# altium-nano-debug.net
KiCad netlist of a schematic drawn in Altium Designer
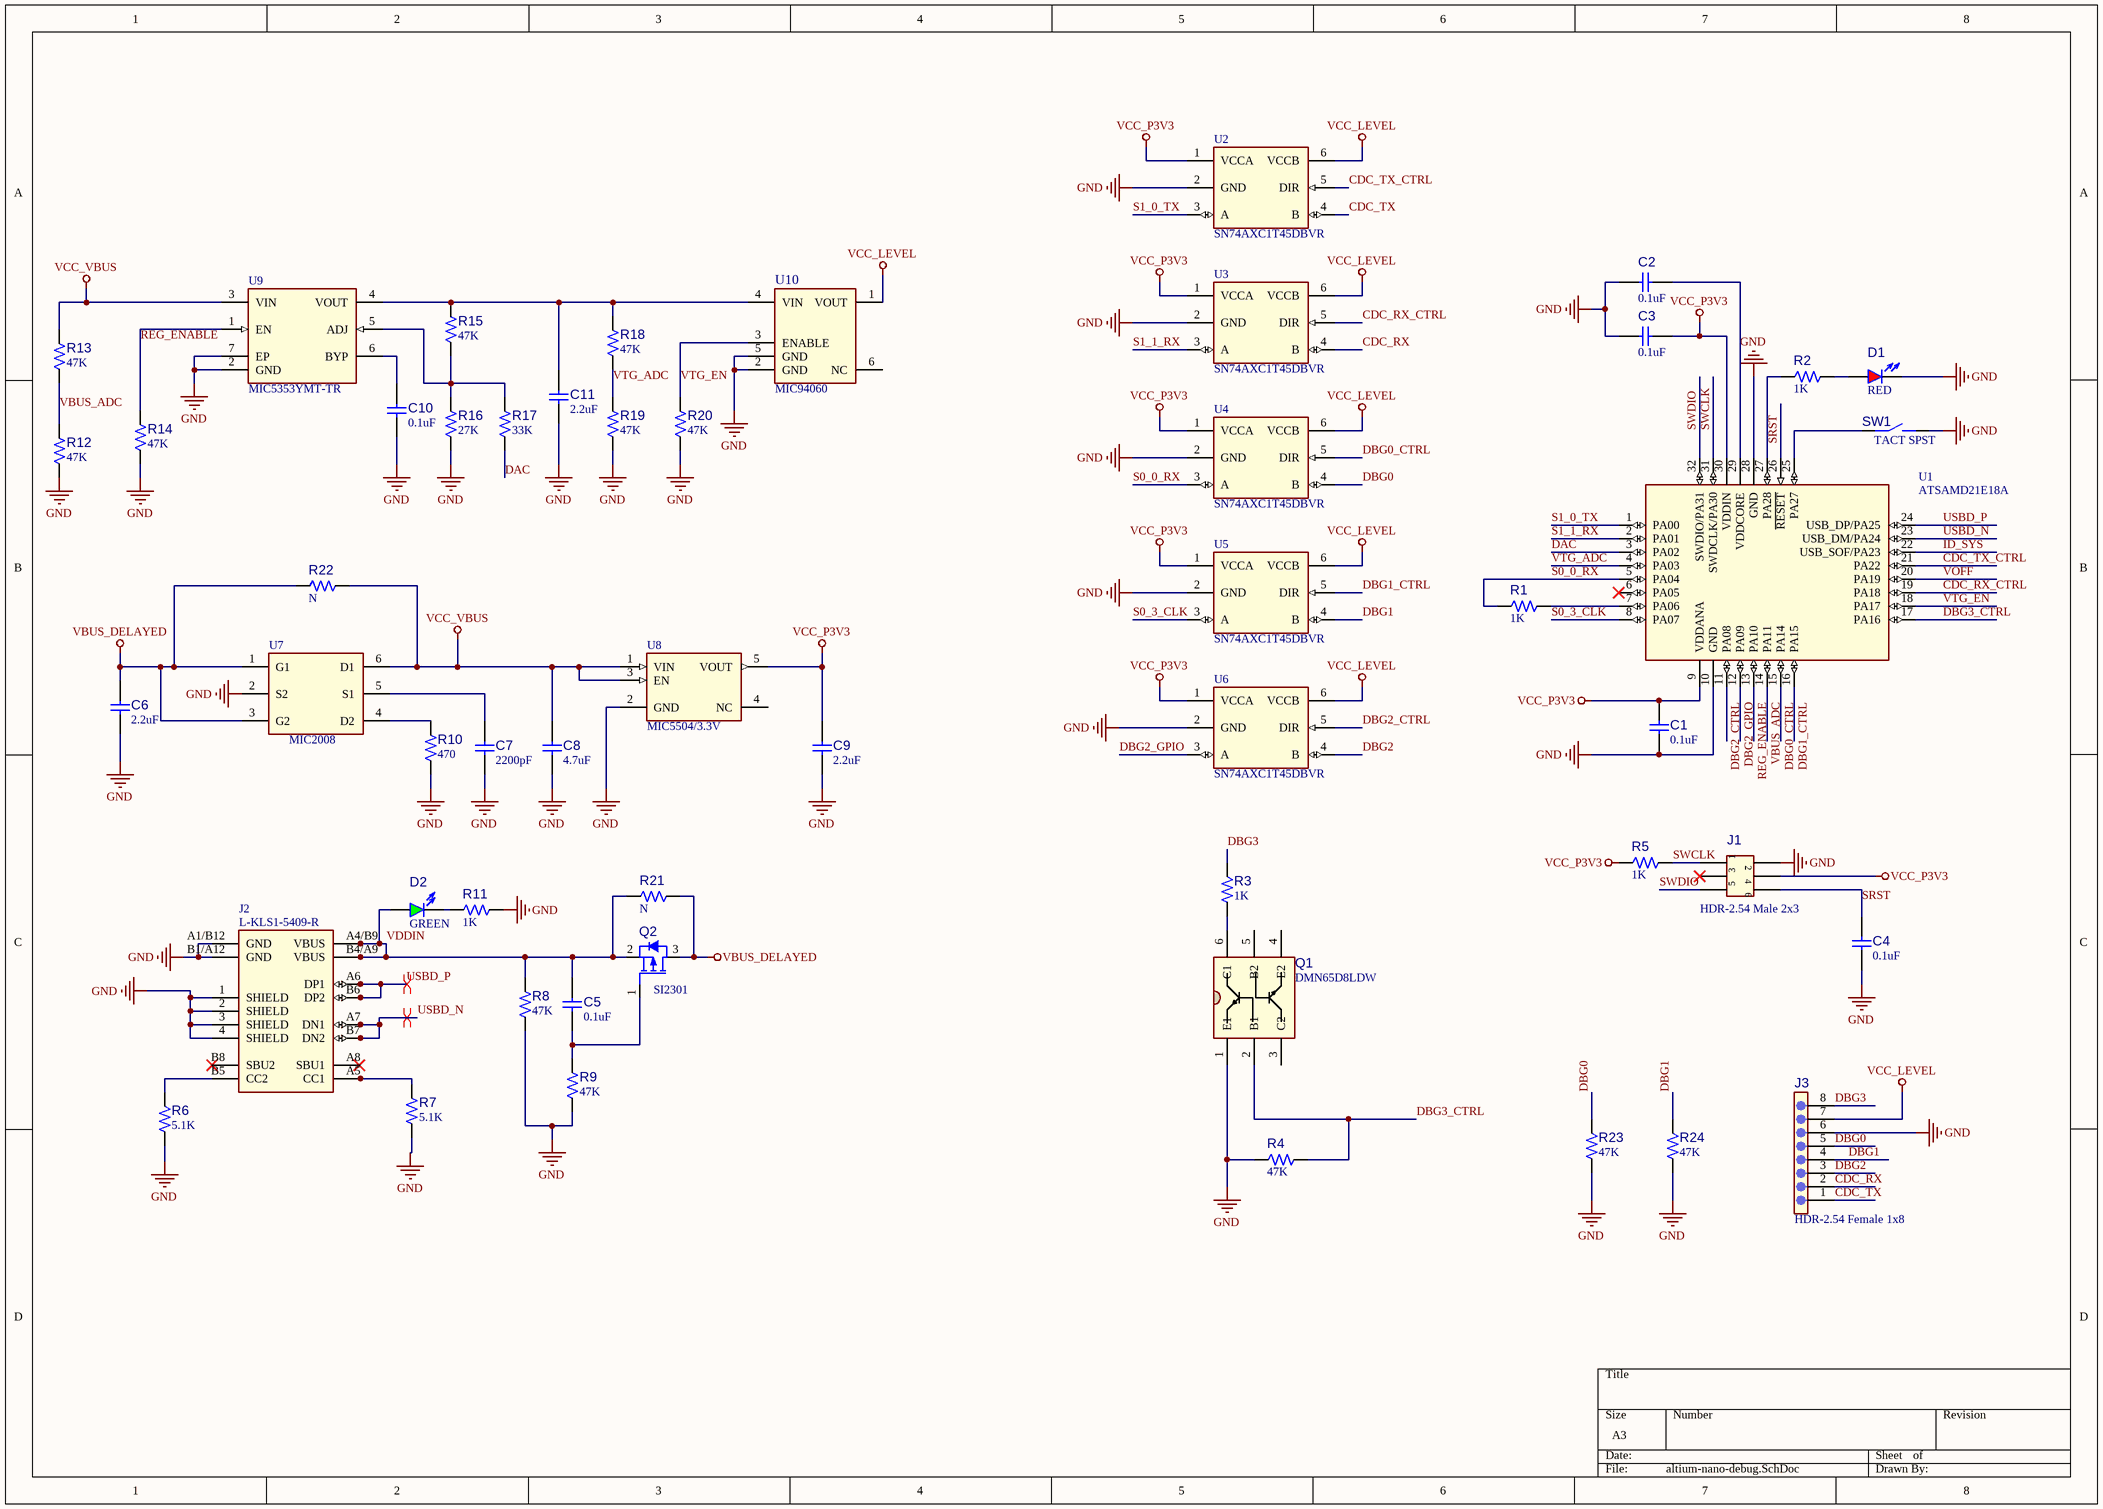
[diagram p0: altium-nano-debug.SchDoc]

(export (version "E")
  (design (tool "Eeschema 10.0.6"))
  (components
    (comp (ref "C1")
      (value "0.1uF")
      (footprint "CAP_C_0603")
      (fields (field (name "TOLERANCE") "20%") (field (name "Comment") "Capacitor NP"))
      (libsource (lib "MCHP-CDB") (part "Capacitor NP"))
    )
    (comp (ref "C2")
      (value "0.1uF")
      (footprint "CAP_C_0603")
      (fields (field (name "TOLERANCE") "20%") (field (name "Comment") "Capacitor NP"))
      (libsource (lib "MCHP-CDB") (part "Capacitor NP"))
    )
    (comp (ref "C3")
      (value "0.1uF")
      (footprint "CAP_C_0603")
      (fields (field (name "TOLERANCE") "20%") (field (name "Comment") "Capacitor NP"))
      (libsource (lib "MCHP-CDB") (part "Capacitor NP"))
    )
    (comp (ref "C4")
      (value "0.1uF")
      (footprint "CAP_C_0603")
      (fields (field (name "TOLERANCE") "20%") (field (name "Comment") "Capacitor NP"))
      (libsource (lib "MCHP-CDB") (part "Capacitor NP"))
    )
    (comp (ref "C5")
      (value "0.1uF")
      (footprint "CAP_C_0603")
      (fields (field (name "TOLERANCE") "20%") (field (name "Comment") "Capacitor NP"))
      (libsource (lib "MCHP-CDB") (part "Capacitor NP"))
    )
    (comp (ref "C6")
      (value "2.2uF")
      (footprint "CAP_C_0603")
      (fields (field (name "TOLERANCE") "20%") (field (name "Comment") "Capacitor NP"))
      (libsource (lib "MCHP-CDB") (part "Capacitor NP"))
    )
    (comp (ref "C7")
      (value "2200pF")
      (footprint "CAP_C_0603")
      (fields (field (name "TOLERANCE") "20%") (field (name "Comment") "Capacitor NP"))
      (libsource (lib "MCHP-CDB") (part "Capacitor NP"))
    )
    (comp (ref "C8")
      (value "4.7uF")
      (footprint "CAP_C_0603")
      (fields (field (name "TOLERANCE") "20%") (field (name "Comment") "Capacitor NP"))
      (libsource (lib "MCHP-CDB") (part "Capacitor NP"))
    )
    (comp (ref "C9")
      (value "2.2uF")
      (footprint "CAP_C_0603")
      (fields (field (name "TOLERANCE") "20%") (field (name "Comment") "Capacitor NP"))
      (libsource (lib "MCHP-CDB") (part "Capacitor NP"))
    )
    (comp (ref "C10")
      (value "0.1uF")
      (footprint "CAP_C_0603")
      (fields (field (name "TOLERANCE") "20%") (field (name "Comment") "Capacitor NP"))
      (libsource (lib "MCHP-CDB") (part "Capacitor NP"))
    )
    (comp (ref "C11")
      (value "2.2uF")
      (footprint "CAP_C_0603")
      (fields (field (name "TOLERANCE") "20%") (field (name "Comment") "Capacitor NP"))
      (libsource (lib "MCHP-CDB") (part "Capacitor NP"))
    )
    (comp (ref "D1")
      (value "RED")
      (footprint "LED_0603_Yellow")
      (description "LED")
      (fields (field (name "POWER") "100mW") (field (name "Comment") "LED_red"))
      (libsource (lib "MCHP-CDB") (part "LED_red"))
    )
    (comp (ref "D2")
      (value "GREEN")
      (footprint "LED_0603_GREEN")
      (description "LED")
      (fields
        (field (name "POWER") "90mW")
        (field (name "Comment") "LED_green")
        (field (name "OWNER") "Severino Balong Jr.")
      )
      (libsource (lib "MCHP-CDB") (part "LED_green"))
    )
    (comp (ref "J1")
      (value "HDR-2.54 Male 2x3")
      (footprint "HDR_M_2.54_2x3")
      (fields (field (name "Comment") "Header 2x3"))
      (libsource (lib "MCHP-CDB") (part "Header 2x3"))
    )
    (comp (ref "J2")
      (value "CON USB2.0-C RCPT SMD RA KLS KLS1-5409")
      (footprint "CON_USB2.0-C_RCPT_SMD_RA_KLS_KLS1-5409")
      (fields (field (name "VOLTAGE") "100V AC") (field (name "MANUFACTURER PART NUMBER 1") "L-KLS1-5409-R"))
      (libsource (lib "MCHP-CDB") (part "CON USB2.0-C RCPT SMD RA KLS KLS1-5409"))
    )
    (comp (ref "J3")
      (value "HDR-2.54 Female 1x8")
      (footprint "HDR_F_2.54_1x8_RA")
      (description "Header 1x8")
      (fields (field (name "OWNER") "Bogdan Popescu"))
      (libsource (lib "MCHP-CDB") (part "Header 1x8"))
    )
    (comp (ref "Q1")
      (value "DMN65D8LDW")
      (footprint "SOT-363")
      (description "ADC")
      (fields
        (field (name "POWER") "200mW")
        (field (name "Comment") "BC847BS-7-F SOT-363")
        (field (name "OWNER") "Jose Garcia")
      )
      (libsource (lib "MCHP-CDB") (part "BC847BS-7-F SOT-363"))
    )
    (comp (ref "Q2")
      (value "SI2301")
      (footprint "SOT-23-3")
      (description "Transistor MOS")
      (fields (field (name "POWER") "1.3W") (field (name "Comment") "Transistor MOS-P GSD"))
      (libsource (lib "MCHP-CDB") (part "Transistor MOS-P GSD"))
    )
    (comp (ref "R1")
      (value "1K")
      (footprint "RES_C_0603")
      (description "Resistor")
      (fields (field (name "VOLTAGE") "50V") (field (name "POWER") "1/10W"))
      (libsource (lib "MCHP-CDB") (part "Resistor"))
    )
    (comp (ref "R2")
      (value "1K")
      (footprint "RES_C_0603")
      (description "Resistor")
      (fields (field (name "VOLTAGE") "50V") (field (name "POWER") "1/10W"))
      (libsource (lib "MCHP-CDB") (part "Resistor"))
    )
    (comp (ref "R3")
      (value "1K")
      (footprint "RES_C_0603")
      (description "Resistor")
      (fields (field (name "VOLTAGE") "50V") (field (name "POWER") "1/10W"))
      (libsource (lib "MCHP-CDB") (part "Resistor"))
    )
    (comp (ref "R4")
      (value "47K")
      (footprint "RES_C_0603")
      (description "Resistor")
      (fields (field (name "VOLTAGE") "50V") (field (name "POWER") "1/10W"))
      (libsource (lib "MCHP-CDB") (part "Resistor"))
    )
    (comp (ref "R5")
      (value "1K")
      (footprint "RES_C_0603")
      (description "Resistor")
      (fields (field (name "VOLTAGE") "50V") (field (name "POWER") "1/10W"))
      (libsource (lib "MCHP-CDB") (part "Resistor"))
    )
    (comp (ref "R6")
      (value "5.1K")
      (footprint "RES_C_0603")
      (description "Resistor")
      (fields (field (name "VOLTAGE") "50V") (field (name "POWER") "1/10W"))
      (libsource (lib "MCHP-CDB") (part "Resistor"))
    )
    (comp (ref "R7")
      (value "5.1K")
      (footprint "RES_C_0603")
      (description "Resistor")
      (fields (field (name "VOLTAGE") "50V") (field (name "POWER") "1/10W"))
      (libsource (lib "MCHP-CDB") (part "Resistor"))
    )
    (comp (ref "R8")
      (value "47K")
      (footprint "RES_C_0603")
      (description "Resistor")
      (fields (field (name "VOLTAGE") "50V") (field (name "POWER") "1/10W"))
      (libsource (lib "MCHP-CDB") (part "Resistor"))
    )
    (comp (ref "R9")
      (value "47K")
      (footprint "RES_C_0603")
      (description "Resistor")
      (fields (field (name "VOLTAGE") "50V") (field (name "POWER") "1/10W"))
      (libsource (lib "MCHP-CDB") (part "Resistor"))
    )
    (comp (ref "R10")
      (value "470")
      (footprint "RES_C_0603")
      (description "Resistor")
      (fields (field (name "VOLTAGE") "50V") (field (name "POWER") "1/10W"))
      (libsource (lib "MCHP-CDB") (part "Resistor"))
    )
    (comp (ref "R11")
      (value "1K")
      (footprint "RES_C_0603")
      (description "Resistor")
      (fields (field (name "VOLTAGE") "50V") (field (name "POWER") "1/10W"))
      (libsource (lib "MCHP-CDB") (part "Resistor"))
    )
    (comp (ref "R12")
      (value "47K")
      (footprint "RES_C_0603")
      (description "Resistor")
      (fields (field (name "VOLTAGE") "50V") (field (name "POWER") "1/10W"))
      (libsource (lib "MCHP-CDB") (part "Resistor"))
    )
    (comp (ref "R13")
      (value "47K")
      (footprint "RES_C_0603")
      (description "Resistor")
      (fields (field (name "VOLTAGE") "50V") (field (name "POWER") "1/10W"))
      (libsource (lib "MCHP-CDB") (part "Resistor"))
    )
    (comp (ref "R14")
      (value "47K")
      (footprint "RES_C_0603")
      (description "Resistor")
      (fields (field (name "VOLTAGE") "50V") (field (name "POWER") "1/10W"))
      (libsource (lib "MCHP-CDB") (part "Resistor"))
    )
    (comp (ref "R15")
      (value "47K")
      (footprint "RES_C_0603")
      (description "Resistor")
      (fields (field (name "VOLTAGE") "50V") (field (name "POWER") "1/10W"))
      (libsource (lib "MCHP-CDB") (part "Resistor"))
    )
    (comp (ref "R16")
      (value "27K")
      (footprint "RES_C_0603")
      (description "Resistor")
      (fields (field (name "VOLTAGE") "50V") (field (name "POWER") "1/10W"))
      (libsource (lib "MCHP-CDB") (part "Resistor"))
    )
    (comp (ref "R17")
      (value "33K")
      (footprint "RES_C_0603")
      (description "Resistor")
      (fields (field (name "VOLTAGE") "50V") (field (name "POWER") "1/10W"))
      (libsource (lib "MCHP-CDB") (part "Resistor"))
    )
    (comp (ref "R18")
      (value "47K")
      (footprint "RES_C_0603")
      (description "Resistor")
      (fields (field (name "VOLTAGE") "50V") (field (name "POWER") "1/10W"))
      (libsource (lib "MCHP-CDB") (part "Resistor"))
    )
    (comp (ref "R19")
      (value "47K")
      (footprint "RES_C_0603")
      (description "Resistor")
      (fields (field (name "VOLTAGE") "50V") (field (name "POWER") "1/10W"))
      (libsource (lib "MCHP-CDB") (part "Resistor"))
    )
    (comp (ref "R20")
      (value "47K")
      (footprint "RES_C_0603")
      (description "Resistor")
      (fields (field (name "VOLTAGE") "50V") (field (name "POWER") "1/10W"))
      (libsource (lib "MCHP-CDB") (part "Resistor"))
    )
    (comp (ref "R21")
      (value "N")
      (footprint "RES_C_0603")
      (description "Resistor")
      (fields (field (name "VOLTAGE") "50V") (field (name "POWER") "1/10W"))
      (libsource (lib "MCHP-CDB") (part "Resistor"))
    )
    (comp (ref "R22")
      (value "N")
      (footprint "RES_C_0603")
      (description "Resistor")
      (fields (field (name "VOLTAGE") "50V") (field (name "POWER") "1/10W"))
      (libsource (lib "MCHP-CDB") (part "Resistor"))
    )
    (comp (ref "R23")
      (value "47K")
      (footprint "RES_C_0603")
      (description "Resistor")
      (fields (field (name "VOLTAGE") "50V") (field (name "POWER") "1/10W"))
      (libsource (lib "MCHP-CDB") (part "Resistor"))
    )
    (comp (ref "R24")
      (value "47K")
      (footprint "RES_C_0603")
      (description "Resistor")
      (fields (field (name "VOLTAGE") "50V") (field (name "POWER") "1/10W"))
      (libsource (lib "MCHP-CDB") (part "Resistor"))
    )
    (comp (ref "SW1")
      (value "TACT SPST")
      (footprint "SW_TACT_SMD_CK_KSR231GLFS")
      (description "Switch")
      (fields
        (field (name "VOLTAGE") "24V")
        (field (name "Comment") "Switch 2 Pin")
        (field (name "OWNER") "Jamus Griego")
      )
      (libsource (lib "MCHP-CDB") (part "Switch 2 Pin"))
    )
    (comp (ref "U1")
      (value "ATSAMD21E18A")
      (footprint "TQFP-32_7x7")
      (description "Microcontroller")
      (fields (field (name "Comment") "ATSAMD21E TQFP-32") (field (name "OWNER") "Vegard  Leksas"))
      (libsource (lib "MCHP-CDB") (part "ATSAMD21E TQFP-32"))
    )
    (comp (ref "U2")
      (value "SN74AXC1T45DBVR")
      (footprint "SOT-23-6")
      (fields (field (name "Comment") "SN74LVC1T45MDCKREP SC-70-6") (field (name "OWNER") "Dragos Danaila"))
      (libsource (lib "MCHP-CDB") (part "SN74LVC1T45MDCKREP SC-70-6"))
    )
    (comp (ref "U3")
      (value "SN74AXC1T45DBVR")
      (footprint "SOT-23-6")
      (fields (field (name "Comment") "SN74LVC1T45MDCKREP SC-70-6") (field (name "OWNER") "Dragos Danaila"))
      (libsource (lib "MCHP-CDB") (part "SN74LVC1T45MDCKREP SC-70-6"))
    )
    (comp (ref "U4")
      (value "SN74AXC1T45DBVR")
      (footprint "SOT-23-6")
      (fields (field (name "Comment") "SN74LVC1T45MDCKREP SC-70-6") (field (name "OWNER") "Dragos Danaila"))
      (libsource (lib "MCHP-CDB") (part "SN74LVC1T45MDCKREP SC-70-6"))
    )
    (comp (ref "U5")
      (value "SN74AXC1T45DBVR")
      (footprint "SOT-23-6")
      (fields (field (name "Comment") "SN74LVC1T45MDCKREP SC-70-6") (field (name "OWNER") "Dragos Danaila"))
      (libsource (lib "MCHP-CDB") (part "SN74LVC1T45MDCKREP SC-70-6"))
    )
    (comp (ref "U6")
      (value "SN74AXC1T45DBVR")
      (footprint "SOT-23-6")
      (fields (field (name "Comment") "SN74LVC1T45MDCKREP SC-70-6") (field (name "OWNER") "Dragos Danaila"))
      (libsource (lib "MCHP-CDB") (part "SN74LVC1T45MDCKREP SC-70-6"))
    )
    (comp (ref "U7")
      (value "MIC2008")
      (footprint "SOT-23-6")
      (fields (field (name "Comment") "AM3906N SOT23-6") (field (name "OWNER") "Jose Garcia"))
      (libsource (lib "MCHP-CDB") (part "AM3906N SOT23-6"))
    )
    (comp (ref "U8")
      (value "MIC5504/3.3V")
      (footprint "SOT-23-5")
      (fields (field (name "Comment") "MIC55XX-X.X SOT23-5") (field (name "OWNER") "Cristina Salanti"))
      (libsource (lib "MCHP-CDB") (part "MIC55XX-X.X SOT23-5"))
    )
    (comp (ref "U9")
      (value "MIC5353YMT-TR")
      (footprint "MLF-6 1.6X1.6mm")
      (description "LDO Regulator")
      (fields (field (name "Comment") "MIC53XX ADJ MLF-6") (field (name "OWNER") "Mark Loper"))
      (libsource (lib "MCHP-CDB") (part "MIC53XX ADJ MLF-6"))
    )
    (comp (ref "U10")
      (value "MIC94060")
      (footprint "SC-70-6")
      (fields (field (name "Comment") "MIC94060Y-SC70-6") (field (name "OWNER") "Sam Charles"))
      (libsource (lib "MCHP-CDB") (part "MIC94060Y-SC70-6"))
    )
  )
  (nets
    (net (code "1") (name "/CDC_RX") (class "Default")
      (node (ref "J3") (pin "2") (pinfunction "2_2") (pintype "passive"))
      (node (ref "U3") (pin "4") (pinfunction "B_4") (pintype "bidirectional"))
    )
    (net (code "2") (name "/CDC_RX_CTRL") (class "Default")
      (node (ref "U1") (pin "19") (pinfunction "PA18_19") (pintype "bidirectional"))
      (node (ref "U3") (pin "5") (pinfunction "DIR_5") (pintype "input"))
    )
    (net (code "3") (name "/CDC_TX") (class "Default")
      (node (ref "J3") (pin "1") (pinfunction "1_1") (pintype "passive"))
      (node (ref "U2") (pin "4") (pinfunction "B_4") (pintype "bidirectional"))
    )
    (net (code "4") (name "/CDC_TX_CTRL") (class "Default")
      (node (ref "U1") (pin "21") (pinfunction "PA22_21") (pintype "bidirectional"))
      (node (ref "U2") (pin "5") (pinfunction "DIR_5") (pintype "input"))
    )
    (net (code "5") (name "/DAC") (class "Default")
      (node (ref "R17") (pin "2") (pinfunction "2_2") (pintype "passive"))
      (node (ref "U1") (pin "3") (pinfunction "PA02_3") (pintype "bidirectional"))
    )
    (net (code "6") (name "/DBG0") (class "Default")
      (node (ref "J3") (pin "5") (pinfunction "5_5") (pintype "passive"))
      (node (ref "R23") (pin "2") (pinfunction "2_2") (pintype "passive"))
      (node (ref "U4") (pin "4") (pinfunction "B_4") (pintype "bidirectional"))
    )
    (net (code "7") (name "/DBG0_CTRL") (class "Default")
      (node (ref "U1") (pin "15") (pinfunction "PA14_15") (pintype "bidirectional"))
      (node (ref "U4") (pin "5") (pinfunction "DIR_5") (pintype "input"))
    )
    (net (code "8") (name "/DBG1") (class "Default")
      (node (ref "J3") (pin "4") (pinfunction "4_4") (pintype "passive"))
      (node (ref "R24") (pin "2") (pinfunction "2_2") (pintype "passive"))
      (node (ref "U5") (pin "4") (pinfunction "B_4") (pintype "bidirectional"))
    )
    (net (code "9") (name "/DBG1_CTRL") (class "Default")
      (node (ref "U1") (pin "16") (pinfunction "PA15_16") (pintype "bidirectional"))
      (node (ref "U5") (pin "5") (pinfunction "DIR_5") (pintype "input"))
    )
    (net (code "10") (name "/DBG2") (class "Default")
      (node (ref "J3") (pin "3") (pinfunction "3_3") (pintype "passive"))
      (node (ref "U6") (pin "4") (pinfunction "B_4") (pintype "bidirectional"))
    )
    (net (code "11") (name "/DBG2_CTRL") (class "Default")
      (node (ref "U1") (pin "11") (pinfunction "PA08_11") (pintype "bidirectional"))
      (node (ref "U6") (pin "5") (pinfunction "DIR_5") (pintype "input"))
    )
    (net (code "12") (name "/DBG2_GPIO") (class "Default")
      (node (ref "U1") (pin "12") (pinfunction "PA09_12") (pintype "bidirectional"))
      (node (ref "U6") (pin "3") (pinfunction "A_3") (pintype "bidirectional"))
    )
    (net (code "13") (name "/DBG3") (class "Default")
      (node (ref "J3") (pin "8") (pinfunction "8_8") (pintype "passive"))
      (node (ref "R3") (pin "2") (pinfunction "2_2") (pintype "passive"))
    )
    (net (code "14") (name "/DBG3_CTRL") (class "Default")
      (node (ref "Q1") (pin "2") (pinfunction "B1_2") (pintype "passive"))
      (node (ref "R4") (pin "2") (pinfunction "2_2") (pintype "passive"))
      (node (ref "U1") (pin "17") (pinfunction "PA16_17") (pintype "bidirectional"))
    )
    (net (code "15") (name "/ID_SYS") (class "Default")
      (node (ref "U1") (pin "22") (pinfunction "USB_SOF/PA23_22") (pintype "bidirectional"))
    )
    (net (code "16") (name "/REG_ENABLE") (class "Default")
      (node (ref "R14") (pin "2") (pinfunction "2_2") (pintype "passive"))
      (node (ref "U1") (pin "13") (pinfunction "PA10_13") (pintype "bidirectional"))
      (node (ref "U9") (pin "1") (pinfunction "EN_1") (pintype "input"))
    )
    (net (code "17") (name "/S0_0_RX") (class "Default")
      (node (ref "R1") (pin "1") (pinfunction "1_1") (pintype "passive"))
      (node (ref "U1") (pin "5") (pinfunction "PA04_5") (pintype "bidirectional"))
      (node (ref "U4") (pin "3") (pinfunction "A_3") (pintype "bidirectional"))
    )
    (net (code "18") (name "/S0_3_CLK") (class "Default")
      (node (ref "U1") (pin "8") (pinfunction "PA07_8") (pintype "bidirectional"))
      (node (ref "U5") (pin "3") (pinfunction "A_3") (pintype "bidirectional"))
    )
    (net (code "19") (name "/S1_0_TX") (class "Default")
      (node (ref "U1") (pin "1") (pinfunction "PA00_1") (pintype "bidirectional"))
      (node (ref "U2") (pin "3") (pinfunction "A_3") (pintype "bidirectional"))
    )
    (net (code "20") (name "/S1_1_RX") (class "Default")
      (node (ref "U1") (pin "2") (pinfunction "PA01_2") (pintype "bidirectional"))
      (node (ref "U3") (pin "3") (pinfunction "A_3") (pintype "bidirectional"))
    )
    (net (code "21") (name "/SRST") (class "Default")
      (node (ref "C4") (pin "2") (pinfunction "2_2") (pintype "passive"))
      (node (ref "J1") (pin "6") (pinfunction "6_6") (pintype "passive"))
      (node (ref "U1") (pin "26") (pinfunction "~{RESET}_26") (pintype "input"))
    )
    (net (code "22") (name "/SWCLK") (class "Default")
      (node (ref "J1") (pin "1") (pinfunction "1_1") (pintype "passive"))
      (node (ref "R5") (pin "1") (pinfunction "1_1") (pintype "passive"))
      (node (ref "U1") (pin "31") (pinfunction "SWDCLK/PA30_31") (pintype "bidirectional"))
    )
    (net (code "23") (name "/SWDIO") (class "Default")
      (node (ref "J1") (pin "5") (pinfunction "5_5") (pintype "passive"))
      (node (ref "U1") (pin "32") (pinfunction "SWDIO/PA31_32") (pintype "bidirectional"))
    )
    (net (code "24") (name "/USBD_N") (class "Default")
      (node (ref "J2") (pin "A7") (pinfunction "DN1_A7") (pintype "bidirectional"))
      (node (ref "J2") (pin "B7") (pinfunction "DN2_B7") (pintype "bidirectional"))
      (node (ref "U1") (pin "23") (pinfunction "USB_DM/PA24_23") (pintype "bidirectional"))
    )
    (net (code "25") (name "/USBD_P") (class "Default")
      (node (ref "J2") (pin "A6") (pinfunction "DP1_A6") (pintype "bidirectional"))
      (node (ref "J2") (pin "B6") (pinfunction "DP2_B6") (pintype "bidirectional"))
      (node (ref "U1") (pin "24") (pinfunction "USB_DP/PA25_24") (pintype "bidirectional"))
    )
    (net (code "26") (name "/VBUS_ADC") (class "Default")
      (node (ref "R12") (pin "2") (pinfunction "2_2") (pintype "passive"))
      (node (ref "R13") (pin "1") (pinfunction "1_1") (pintype "passive"))
      (node (ref "U1") (pin "14") (pinfunction "PA11_14") (pintype "bidirectional"))
    )
    (net (code "27") (name "/VDDIN") (class "Default")
      (node (ref "C5") (pin "1") (pinfunction "1_1") (pintype "passive"))
      (node (ref "D2") (pin "1") (pinfunction "A_1") (pintype "passive"))
      (node (ref "J2") (pin "A4/B9") (pinfunction "VBUS_A4/B9") (pintype "power_in"))
      (node (ref "J2") (pin "B4/A9") (pinfunction "VBUS_B4/A9") (pintype "power_in"))
      (node (ref "Q2") (pin "2") (pinfunction "S_2") (pintype "passive"))
      (node (ref "R21") (pin "2") (pinfunction "2_2") (pintype "passive"))
      (node (ref "R8") (pin "2") (pinfunction "2_2") (pintype "passive"))
    )
    (net (code "28") (name "/VOFF") (class "Default")
      (node (ref "U1") (pin "20") (pinfunction "PA19_20") (pintype "bidirectional"))
    )
    (net (code "29") (name "/VTG_ADC") (class "Default")
      (node (ref "R18") (pin "1") (pinfunction "1_1") (pintype "passive"))
      (node (ref "R19") (pin "2") (pinfunction "2_2") (pintype "passive"))
      (node (ref "U1") (pin "4") (pinfunction "PA03_4") (pintype "bidirectional"))
    )
    (net (code "30") (name "/VTG_EN") (class "Default")
      (node (ref "R20") (pin "2") (pinfunction "2_2") (pintype "passive"))
      (node (ref "U1") (pin "18") (pinfunction "PA17_18") (pintype "bidirectional"))
      (node (ref "U10") (pin "3") (pinfunction "ENABLE_3") (pintype "passive"))
    )
    (net (code "31") (name "GND") (class "Default")
      (node (ref "C1") (pin "1") (pinfunction "1_1") (pintype "passive"))
      (node (ref "C10") (pin "2") (pinfunction "2_2") (pintype "passive"))
      (node (ref "C11") (pin "2") (pinfunction "2_2") (pintype "passive"))
      (node (ref "C2") (pin "1") (pinfunction "1_1") (pintype "passive"))
      (node (ref "C3") (pin "1") (pinfunction "1_1") (pintype "passive"))
      (node (ref "C4") (pin "1") (pinfunction "1_1") (pintype "passive"))
      (node (ref "C6") (pin "2") (pinfunction "2_2") (pintype "passive"))
      (node (ref "C7") (pin "2") (pinfunction "2_2") (pintype "passive"))
      (node (ref "C8") (pin "2") (pinfunction "2_2") (pintype "passive"))
      (node (ref "C9") (pin "2") (pinfunction "2_2") (pintype "passive"))
      (node (ref "D1") (pin "2") (pinfunction "K_2") (pintype "passive"))
      (node (ref "J1") (pin "2") (pinfunction "2_2") (pintype "passive"))
      (node (ref "J2") (pin "1") (pinfunction "SHIELD_1") (pintype "passive"))
      (node (ref "J2") (pin "2") (pinfunction "SHIELD_2") (pintype "passive"))
      (node (ref "J2") (pin "3") (pinfunction "SHIELD_3") (pintype "passive"))
      (node (ref "J2") (pin "4") (pinfunction "SHIELD_4") (pintype "passive"))
      (node (ref "J2") (pin "A1/B12") (pinfunction "GND_A1/B12") (pintype "power_in"))
      (node (ref "J2") (pin "B1/A12") (pinfunction "GND_B1/A12") (pintype "power_in"))
      (node (ref "J3") (pin "6") (pinfunction "6_6") (pintype "passive"))
      (node (ref "Q1") (pin "1") (pinfunction "E1_1") (pintype "passive"))
      (node (ref "R10") (pin "1") (pinfunction "1_1") (pintype "passive"))
      (node (ref "R11") (pin "1") (pinfunction "1_1") (pintype "passive"))
      (node (ref "R12") (pin "1") (pinfunction "1_1") (pintype "passive"))
      (node (ref "R14") (pin "1") (pinfunction "1_1") (pintype "passive"))
      (node (ref "R16") (pin "1") (pinfunction "1_1") (pintype "passive"))
      (node (ref "R19") (pin "1") (pinfunction "1_1") (pintype "passive"))
      (node (ref "R20") (pin "1") (pinfunction "1_1") (pintype "passive"))
      (node (ref "R23") (pin "1") (pinfunction "1_1") (pintype "passive"))
      (node (ref "R24") (pin "1") (pinfunction "1_1") (pintype "passive"))
      (node (ref "R4") (pin "1") (pinfunction "1_1") (pintype "passive"))
      (node (ref "R6") (pin "2") (pinfunction "2_2") (pintype "passive"))
      (node (ref "R7") (pin "2") (pinfunction "2_2") (pintype "passive"))
      (node (ref "R8") (pin "1") (pinfunction "1_1") (pintype "passive"))
      (node (ref "R9") (pin "1") (pinfunction "1_1") (pintype "passive"))
      (node (ref "SW1") (pin "2") (pinfunction "2_2") (pintype "passive"))
      (node (ref "U1") (pin "10") (pinfunction "GND_10") (pintype "power_in"))
      (node (ref "U1") (pin "28") (pinfunction "GND_28") (pintype "power_in"))
      (node (ref "U10") (pin "2") (pinfunction "GND_2") (pintype "passive"))
      (node (ref "U10") (pin "5") (pinfunction "GND_5") (pintype "passive"))
      (node (ref "U2") (pin "2") (pinfunction "GND_2") (pintype "power_in"))
      (node (ref "U3") (pin "2") (pinfunction "GND_2") (pintype "power_in"))
      (node (ref "U4") (pin "2") (pinfunction "GND_2") (pintype "power_in"))
      (node (ref "U5") (pin "2") (pinfunction "GND_2") (pintype "power_in"))
      (node (ref "U6") (pin "2") (pinfunction "GND_2") (pintype "power_in"))
      (node (ref "U7") (pin "2") (pinfunction "S2_2") (pintype "power_in"))
      (node (ref "U8") (pin "2") (pinfunction "GND_2") (pintype "passive"))
      (node (ref "U9") (pin "2") (pinfunction "GND_2") (pintype "power_in"))
      (node (ref "U9") (pin "7") (pinfunction "EP_7") (pintype "passive"))
    )
    (net (code "32") (name "Net-(D1-A)") (class "Default")
      (node (ref "D1") (pin "1") (pinfunction "A_1") (pintype "passive"))
      (node (ref "R2") (pin "1") (pinfunction "1_1") (pintype "passive"))
    )
    (net (code "33") (name "Net-(D2-K)") (class "Default")
      (node (ref "D2") (pin "2") (pinfunction "K_2") (pintype "passive"))
      (node (ref "R11") (pin "2") (pinfunction "2_2") (pintype "passive"))
    )
    (net (code "34") (name "Net-(J2-CC1)") (class "Default")
      (node (ref "J2") (pin "A5") (pinfunction "CC1_A5") (pintype "passive"))
      (node (ref "R7") (pin "1") (pinfunction "1_1") (pintype "passive"))
    )
    (net (code "35") (name "Net-(J2-CC2)") (class "Default")
      (node (ref "J2") (pin "B5") (pinfunction "CC2_B5") (pintype "passive"))
      (node (ref "R6") (pin "1") (pinfunction "1_1") (pintype "passive"))
    )
    (net (code "36") (name "Net-(Q1-C1)") (class "Default")
      (node (ref "Q1") (pin "6") (pinfunction "C1_6") (pintype "passive"))
      (node (ref "R3") (pin "1") (pinfunction "1_1") (pintype "passive"))
    )
    (net (code "37") (name "Net-(Q2-G)") (class "Default")
      (node (ref "C5") (pin "2") (pinfunction "2_2") (pintype "passive"))
      (node (ref "Q2") (pin "1") (pinfunction "G_1") (pintype "passive"))
      (node (ref "R9") (pin "2") (pinfunction "2_2") (pintype "passive"))
    )
    (net (code "38") (name "Net-(U1-PA06)") (class "Default")
      (node (ref "R1") (pin "2") (pinfunction "2_2") (pintype "passive"))
      (node (ref "U1") (pin "7") (pinfunction "PA06_7") (pintype "bidirectional"))
    )
    (net (code "39") (name "Net-(U1-PA27)") (class "Default")
      (node (ref "SW1") (pin "1") (pinfunction "1_1") (pintype "passive"))
      (node (ref "U1") (pin "25") (pinfunction "PA27_25") (pintype "bidirectional"))
    )
    (net (code "40") (name "Net-(U1-PA28)") (class "Default")
      (node (ref "R2") (pin "2") (pinfunction "2_2") (pintype "passive"))
      (node (ref "U1") (pin "27") (pinfunction "PA28_27") (pintype "bidirectional"))
    )
    (net (code "41") (name "Net-(U1-VDDCORE)") (class "Default")
      (node (ref "C2") (pin "2") (pinfunction "2_2") (pintype "passive"))
      (node (ref "U1") (pin "29") (pinfunction "VDDCORE_29") (pintype "power_in"))
    )
    (net (code "42") (name "Net-(U7-D2)") (class "Default")
      (node (ref "R10") (pin "2") (pinfunction "2_2") (pintype "passive"))
      (node (ref "U7") (pin "4") (pinfunction "D2_4") (pintype "passive"))
    )
    (net (code "43") (name "Net-(U7-S1)") (class "Default")
      (node (ref "C7") (pin "1") (pinfunction "1_1") (pintype "passive"))
      (node (ref "U7") (pin "5") (pinfunction "S1_5") (pintype "passive"))
    )
    (net (code "44") (name "Net-(U9-ADJ)") (class "Default")
      (node (ref "R15") (pin "1") (pinfunction "1_1") (pintype "passive"))
      (node (ref "R16") (pin "2") (pinfunction "2_2") (pintype "passive"))
      (node (ref "R17") (pin "1") (pinfunction "1_1") (pintype "passive"))
      (node (ref "U9") (pin "5") (pinfunction "ADJ_5") (pintype "input"))
    )
    (net (code "45") (name "Net-(U9-BYP)") (class "Default")
      (node (ref "C10") (pin "1") (pinfunction "1_1") (pintype "passive"))
      (node (ref "U9") (pin "6") (pinfunction "BYP_6") (pintype "power_in"))
    )
    (net (code "46") (name "Net-(U10-VIN)") (class "Default")
      (node (ref "C11") (pin "1") (pinfunction "1_1") (pintype "passive"))
      (node (ref "R15") (pin "2") (pinfunction "2_2") (pintype "passive"))
      (node (ref "R18") (pin "2") (pinfunction "2_2") (pintype "passive"))
      (node (ref "U10") (pin "4") (pinfunction "VIN_4") (pintype "passive"))
      (node (ref "U9") (pin "4") (pinfunction "VOUT_4") (pintype "power_in"))
    )
    (net (code "47") (name "VBUS_DELAYED") (class "Default")
      (node (ref "C6") (pin "1") (pinfunction "1_1") (pintype "passive"))
      (node (ref "Q2") (pin "3") (pinfunction "D_3") (pintype "passive"))
      (node (ref "R21") (pin "1") (pinfunction "1_1") (pintype "passive"))
      (node (ref "R22") (pin "2") (pinfunction "2_2") (pintype "passive"))
      (node (ref "U7") (pin "1") (pinfunction "G1_1") (pintype "power_in"))
      (node (ref "U7") (pin "3") (pinfunction "G2_3") (pintype "passive"))
    )
    (net (code "48") (name "VCC_LEVEL") (class "Default")
      (node (ref "J3") (pin "7") (pinfunction "7_7") (pintype "passive"))
      (node (ref "U10") (pin "1") (pinfunction "VOUT_1") (pintype "passive"))
      (node (ref "U2") (pin "6") (pinfunction "VCCB_6") (pintype "power_in"))
      (node (ref "U3") (pin "6") (pinfunction "VCCB_6") (pintype "power_in"))
      (node (ref "U4") (pin "6") (pinfunction "VCCB_6") (pintype "power_in"))
      (node (ref "U5") (pin "6") (pinfunction "VCCB_6") (pintype "power_in"))
      (node (ref "U6") (pin "6") (pinfunction "VCCB_6") (pintype "power_in"))
    )
    (net (code "49") (name "VCC_P3V3") (class "Default")
      (node (ref "C1") (pin "2") (pinfunction "2_2") (pintype "passive"))
      (node (ref "C3") (pin "2") (pinfunction "2_2") (pintype "passive"))
      (node (ref "C9") (pin "1") (pinfunction "1_1") (pintype "passive"))
      (node (ref "J1") (pin "4") (pinfunction "4_4") (pintype "passive"))
      (node (ref "R5") (pin "2") (pinfunction "2_2") (pintype "passive"))
      (node (ref "U1") (pin "30") (pinfunction "VDDIN_30") (pintype "power_in"))
      (node (ref "U1") (pin "9") (pinfunction "VDDANA_9") (pintype "power_in"))
      (node (ref "U2") (pin "1") (pinfunction "VCCA_1") (pintype "power_in"))
      (node (ref "U3") (pin "1") (pinfunction "VCCA_1") (pintype "power_in"))
      (node (ref "U4") (pin "1") (pinfunction "VCCA_1") (pintype "power_in"))
      (node (ref "U5") (pin "1") (pinfunction "VCCA_1") (pintype "power_in"))
      (node (ref "U6") (pin "1") (pinfunction "VCCA_1") (pintype "power_in"))
      (node (ref "U8") (pin "5") (pinfunction "VOUT_5") (pintype "output"))
    )
    (net (code "50") (name "VCC_VBUS") (class "Default")
      (node (ref "C8") (pin "1") (pinfunction "1_1") (pintype "passive"))
      (node (ref "R13") (pin "2") (pinfunction "2_2") (pintype "passive"))
      (node (ref "R22") (pin "1") (pinfunction "1_1") (pintype "passive"))
      (node (ref "U7") (pin "6") (pinfunction "D1_6") (pintype "power_in"))
      (node (ref "U8") (pin "1") (pinfunction "VIN_1") (pintype "input"))
      (node (ref "U8") (pin "3") (pinfunction "EN_3") (pintype "input"))
      (node (ref "U9") (pin "3") (pinfunction "VIN_3") (pintype "power_in"))
    )
    (net (code "51") (name "unconnected-(J1-Pad3)") (class "Default")
      (node (ref "J1") (pin "3") (pinfunction "3_3") (pintype "passive+no_connect"))
    )
    (net (code "52") (name "unconnected-(J2-SBU1-PadA8)") (class "Default")
      (node (ref "J2") (pin "A8") (pinfunction "SBU1_A8") (pintype "passive"))
    )
    (net (code "53") (name "unconnected-(J2-SBU2-PadB8)") (class "Default")
      (node (ref "J2") (pin "B8") (pinfunction "SBU2_B8") (pintype "passive+no_connect"))
    )
    (net (code "54") (name "unconnected-(Q1-B2-Pad5)") (class "Default")
      (node (ref "Q1") (pin "5") (pinfunction "B2_5") (pintype "passive"))
    )
    (net (code "55") (name "unconnected-(Q1-C2-Pad3)") (class "Default")
      (node (ref "Q1") (pin "3") (pinfunction "C2_3") (pintype "passive"))
    )
    (net (code "56") (name "unconnected-(Q1-E2-Pad4)") (class "Default")
      (node (ref "Q1") (pin "4") (pinfunction "E2_4") (pintype "passive"))
    )
    (net (code "57") (name "unconnected-(U1-PA05-Pad6)") (class "Default")
      (node (ref "U1") (pin "6") (pinfunction "PA05_6") (pintype "bidirectional+no_connect"))
    )
    (net (code "58") (name "unconnected-(U8-NC-Pad4)") (class "Default")
      (node (ref "U8") (pin "4") (pinfunction "NC_4") (pintype "passive"))
    )
    (net (code "59") (name "unconnected-(U10-NC-Pad6)") (class "Default")
      (node (ref "U10") (pin "6") (pinfunction "NC_6") (pintype "passive"))
    )
  )
)
